# GNSS_PPS_LED_Driver.net
KiCad netlist of a schematic drawn in Altium Designer
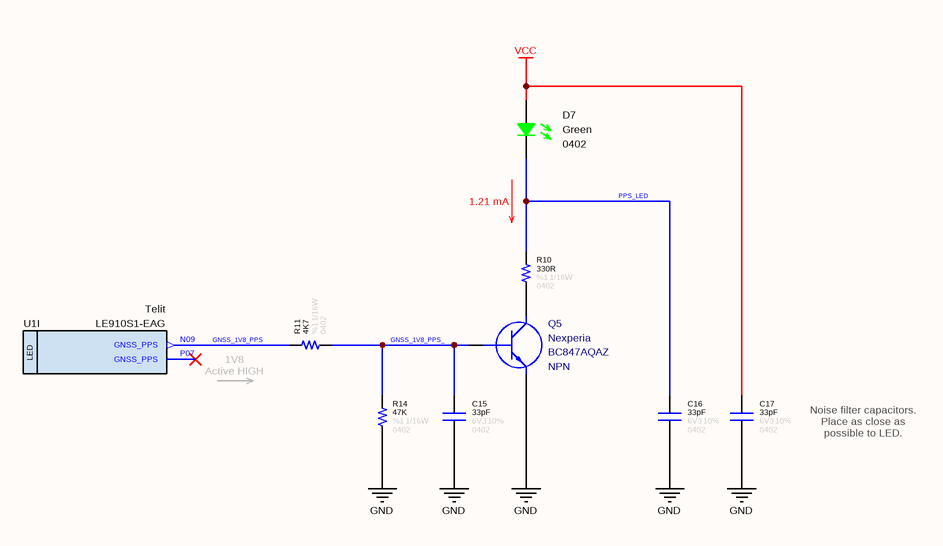
[diagram p0: GNSS PPS LED Driver.SchDoc]

(export (version "E")
  (design (tool "Eeschema 10.0.6"))
  (components
    (comp (ref "C15")
      (value "33pF")
      (footprint "CAPACITOR_0402")
      (description "Capacitor - 33pF [0402] (Ceramic)")
      (fields
        (field (name "MANUFACTURER PART NUMBER") "C0402C330J9RACAUTO")
        (field (name "TOLERANCE") "10%")
        (field (name "CASE") "0402")
        (field (name "VOLTAGE") "6V3")
      )
      (libsource (lib "P101DA_Library") (part "Capacitor - 33pF [0402-6V3]"))
    )
    (comp (ref "C16")
      (value "33pF")
      (footprint "CAPACITOR_0402")
      (description "Capacitor - 33pF [0402] (Ceramic)")
      (fields
        (field (name "MANUFACTURER PART NUMBER") "C0402C330J9RACAUTO")
        (field (name "TOLERANCE") "10%")
        (field (name "CASE") "0402")
        (field (name "VOLTAGE") "6V3")
      )
      (libsource (lib "P101DA_Library") (part "Capacitor - 33pF [0402-6V3]"))
    )
    (comp (ref "C17")
      (value "33pF")
      (footprint "CAPACITOR_0402")
      (description "Capacitor - 33pF [0402] (Ceramic)")
      (fields
        (field (name "MANUFACTURER PART NUMBER") "C0402C330J9RACAUTO")
        (field (name "TOLERANCE") "10%")
        (field (name "CASE") "0402")
        (field (name "VOLTAGE") "6V3")
      )
      (libsource (lib "P101DA_Library") (part "Capacitor - 33pF [0402-6V3]"))
    )
    (comp (ref "D7")
      (value "SMD LED (Green)")
      (footprint "LED_0402")
      (description "Standard LEDs - SMD MINI-MOLD ULTRA COMPACT GREEN")
      (fields
        (field (name "MANUFACTURER PART NUMBER") "SML-P12MTT86R")
        (field (name "CASE") "0402")
        (field (name "COLOR") "Green")
      )
      (libsource (lib "P101DA_Library") (part "Diode - LED (0402-Green)"))
    )
    (comp (ref "Q5")
      (value "BC847AQAZ")
      (footprint "SOT1215")
      (description "Bipolar NPN Transistors")
      (fields
        (field (name "MANUFACTURER NAME") "Nexperia")
        (field (name "MANUFACTURER PART NUMBER") "BC847AQAZ")
        (field (name "POLARITY") "NPN")
      )
      (libsource (lib "P101DA_Library") (part "Transistor - BC847"))
    )
    (comp (ref "R10")
      (value "330R")
      (footprint "RESISTOR_0402")
      (description "Thick Film Resistors - SMD 1/16 W 330 Ohm 1%")
      (fields
        (field (name "MANUFACTURER PART NUMBER") "CRCW0402330RFKED")
        (field (name "CASE") "0402")
        (field (name "TOLERANCE") "%1")
        (field (name "POWER") "1/16W")
        (field (name "Comment") "330R - 0402 - %1 - 1/16W")
      )
      (libsource (lib "P101DA_Library") (part "Resistor - 330R [0402]"))
    )
    (comp (ref "R11")
      (value "4K7")
      (footprint "RESISTOR_0402")
      (description "Thick Film Resistors - SMD 1/16 W 4.7 KOhm 1%")
      (fields
        (field (name "MANUFACTURER PART NUMBER") "CRCW04024K70FKED")
        (field (name "TOLERANCE") "%1")
        (field (name "CASE") "0402")
        (field (name "POWER") "1/16W")
        (field (name "Comment") "4K7 - 0402 - %1 - 1/16W")
      )
      (libsource (lib "P101DA_Library") (part "Resistor - 4K7 [0402]"))
    )
    (comp (ref "R14")
      (value "47K")
      (footprint "RESISTOR_0402")
      (description "Thick Film Resistors - SMD 1/16 W 47 KOhm 1%")
      (fields
        (field (name "MANUFACTURER PART NUMBER") "CRCW040247K0FKED")
        (field (name "TOLERANCE") "%1")
        (field (name "CASE") "0402")
        (field (name "POWER") "1/16W")
        (field (name "Comment") "47K - 0402 - %1 - 1/16W")
      )
      (libsource (lib "P101DA_Library") (part "Resistor - 47K [0402]"))
    )
    (comp (ref "U1")
      (value "LE910S1-EAG LTE GSM Module")
      (footprint "LE910 GSM Modem")
      (description "Telit LE910S1-EAG GPRS/GNSS Module")
      (fields
        (field (name "MANUFACTURER PART NUMBER") "LE910S1-EAG")
        (field (name "MANUFACTURER NAME") "Telit")
      )
      (libsource (lib "P101DA_Library") (part "IC - LE910S1-EAG"))
    )
  )
  (nets
    (net (code "1") (name "/GNSS_1V8_PPS") (class "Default")
      (node (ref "R11") (pin "2") (pinfunction "2_2") (pintype "passive"))
      (node (ref "U1") (pin "N09") (pinfunction "GNSS_PPS_N09") (pintype "output"))
    )
    (net (code "2") (name "/GNSS_1V8_PPS_") (class "Default")
      (node (ref "C15") (pin "2") (pinfunction "2_2") (pintype "passive"))
      (node (ref "Q5") (pin "1") (pinfunction "B_1") (pintype "passive"))
      (node (ref "R11") (pin "1") (pinfunction "1_1") (pintype "passive"))
      (node (ref "R14") (pin "2") (pinfunction "2_2") (pintype "passive"))
    )
    (net (code "3") (name "/PPS_LED") (class "Default")
      (node (ref "C16") (pin "2") (pinfunction "2_2") (pintype "passive"))
      (node (ref "D7") (pin "1") (pinfunction "1_1") (pintype "passive"))
      (node (ref "R10") (pin "2") (pinfunction "2_2") (pintype "passive"))
    )
    (net (code "4") (name "GND") (class "Default")
      (node (ref "C15") (pin "1") (pinfunction "1_1") (pintype "passive"))
      (node (ref "C16") (pin "1") (pinfunction "1_1") (pintype "passive"))
      (node (ref "C17") (pin "1") (pinfunction "1_1") (pintype "passive"))
      (node (ref "Q5") (pin "2") (pinfunction "E_2") (pintype "passive"))
      (node (ref "R14") (pin "1") (pinfunction "1_1") (pintype "passive"))
    )
    (net (code "5") (name "Net-(Q5-C)") (class "Default")
      (node (ref "Q5") (pin "3") (pinfunction "C_3") (pintype "passive"))
      (node (ref "R10") (pin "1") (pinfunction "1_1") (pintype "passive"))
    )
    (net (code "6") (name "VCC") (class "Default")
      (node (ref "C17") (pin "2") (pinfunction "2_2") (pintype "passive"))
      (node (ref "D7") (pin "2") (pinfunction "2_2") (pintype "passive"))
    )
    (net (code "7") (name "unconnected-(U1I-GNSS_PPS-PadP07)") (class "Default")
      (node (ref "U1") (pin "P07") (pinfunction "GNSS_PPS_P07") (pintype "passive+no_connect"))
    )
  )
)
